# matrix.net
KiCad netlist of a schematic drawn in Altium Designer
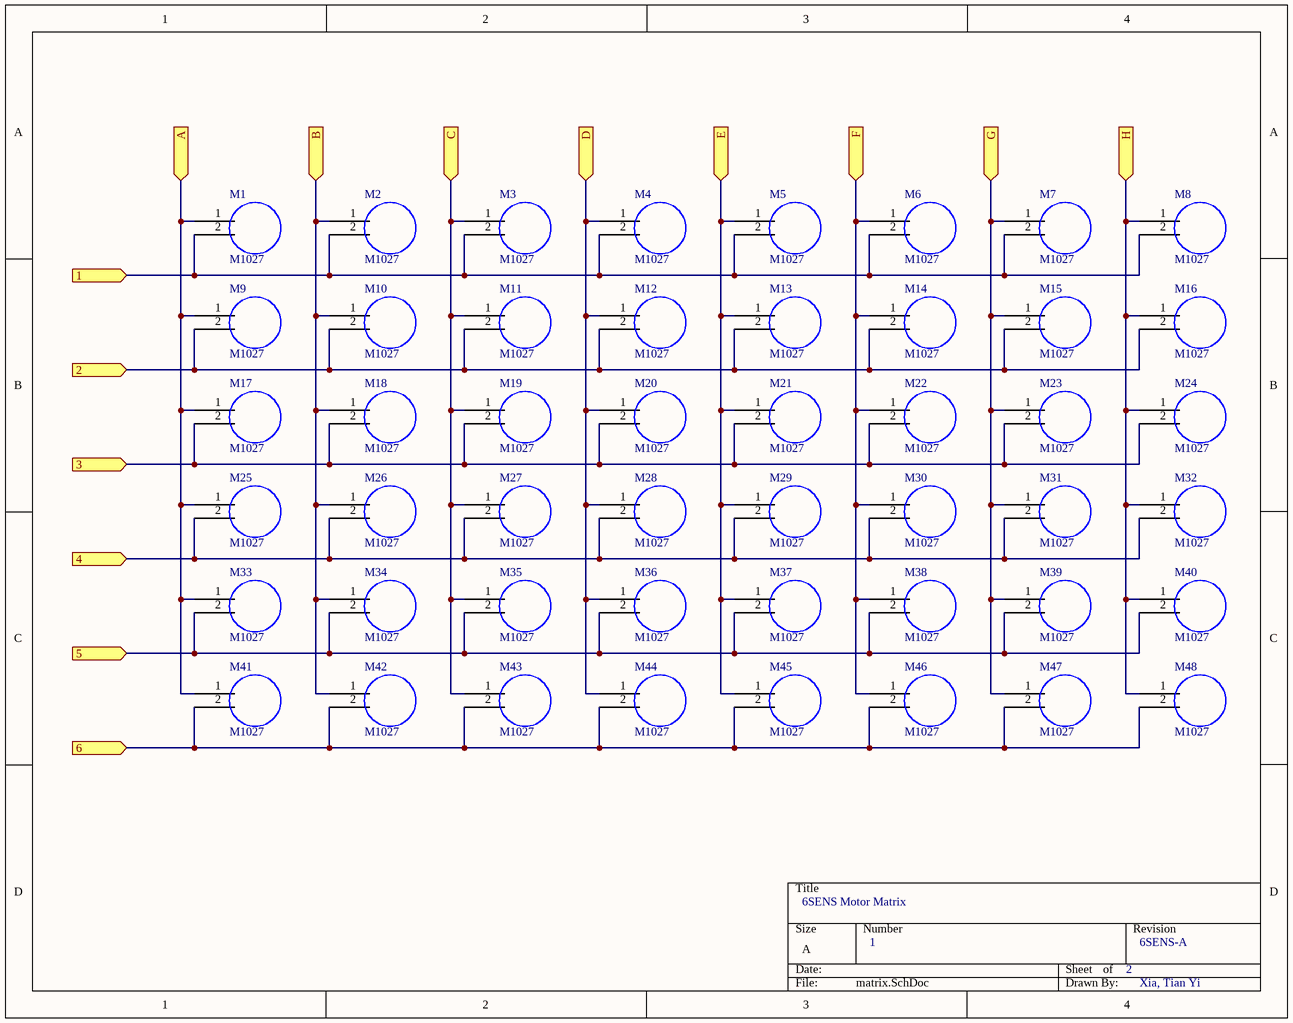
[diagram p0: matrix.SchDoc]

(export (version "E")
  (design (tool "Eeschema 10.0.6"))
  (components
    (comp (ref "M1")
      (value "M1027")
      (footprint "M1027")
      (description "10mm x 2.7mm vibration motor")
      (libsource (lib "6thsense_lib") (part "M1027"))
    )
    (comp (ref "M2")
      (value "M1027")
      (footprint "M1027")
      (description "10mm x 2.7mm vibration motor")
      (libsource (lib "6thsense_lib") (part "M1027"))
    )
    (comp (ref "M3")
      (value "M1027")
      (footprint "M1027")
      (description "10mm x 2.7mm vibration motor")
      (libsource (lib "6thsense_lib") (part "M1027"))
    )
    (comp (ref "M4")
      (value "M1027")
      (footprint "M1027")
      (description "10mm x 2.7mm vibration motor")
      (libsource (lib "6thsense_lib") (part "M1027"))
    )
    (comp (ref "M5")
      (value "M1027")
      (footprint "M1027")
      (description "10mm x 2.7mm vibration motor")
      (libsource (lib "6thsense_lib") (part "M1027"))
    )
    (comp (ref "M6")
      (value "M1027")
      (footprint "M1027")
      (description "10mm x 2.7mm vibration motor")
      (libsource (lib "6thsense_lib") (part "M1027"))
    )
    (comp (ref "M7")
      (value "M1027")
      (footprint "M1027")
      (description "10mm x 2.7mm vibration motor")
      (libsource (lib "6thsense_lib") (part "M1027"))
    )
    (comp (ref "M8")
      (value "M1027")
      (footprint "M1027")
      (description "10mm x 2.7mm vibration motor")
      (libsource (lib "6thsense_lib") (part "M1027"))
    )
    (comp (ref "M9")
      (value "M1027")
      (footprint "M1027")
      (description "10mm x 2.7mm vibration motor")
      (libsource (lib "6thsense_lib") (part "M1027"))
    )
    (comp (ref "M10")
      (value "M1027")
      (footprint "M1027")
      (description "10mm x 2.7mm vibration motor")
      (libsource (lib "6thsense_lib") (part "M1027"))
    )
    (comp (ref "M11")
      (value "M1027")
      (footprint "M1027")
      (description "10mm x 2.7mm vibration motor")
      (libsource (lib "6thsense_lib") (part "M1027"))
    )
    (comp (ref "M12")
      (value "M1027")
      (footprint "M1027")
      (description "10mm x 2.7mm vibration motor")
      (libsource (lib "6thsense_lib") (part "M1027"))
    )
    (comp (ref "M13")
      (value "M1027")
      (footprint "M1027")
      (description "10mm x 2.7mm vibration motor")
      (libsource (lib "6thsense_lib") (part "M1027"))
    )
    (comp (ref "M14")
      (value "M1027")
      (footprint "M1027")
      (description "10mm x 2.7mm vibration motor")
      (libsource (lib "6thsense_lib") (part "M1027"))
    )
    (comp (ref "M15")
      (value "M1027")
      (footprint "M1027")
      (description "10mm x 2.7mm vibration motor")
      (libsource (lib "6thsense_lib") (part "M1027"))
    )
    (comp (ref "M16")
      (value "M1027")
      (footprint "M1027")
      (description "10mm x 2.7mm vibration motor")
      (libsource (lib "6thsense_lib") (part "M1027"))
    )
    (comp (ref "M17")
      (value "M1027")
      (footprint "M1027")
      (description "10mm x 2.7mm vibration motor")
      (libsource (lib "6thsense_lib") (part "M1027"))
    )
    (comp (ref "M18")
      (value "M1027")
      (footprint "M1027")
      (description "10mm x 2.7mm vibration motor")
      (libsource (lib "6thsense_lib") (part "M1027"))
    )
    (comp (ref "M19")
      (value "M1027")
      (footprint "M1027")
      (description "10mm x 2.7mm vibration motor")
      (libsource (lib "6thsense_lib") (part "M1027"))
    )
    (comp (ref "M20")
      (value "M1027")
      (footprint "M1027")
      (description "10mm x 2.7mm vibration motor")
      (libsource (lib "6thsense_lib") (part "M1027"))
    )
    (comp (ref "M21")
      (value "M1027")
      (footprint "M1027")
      (description "10mm x 2.7mm vibration motor")
      (libsource (lib "6thsense_lib") (part "M1027"))
    )
    (comp (ref "M22")
      (value "M1027")
      (footprint "M1027")
      (description "10mm x 2.7mm vibration motor")
      (libsource (lib "6thsense_lib") (part "M1027"))
    )
    (comp (ref "M23")
      (value "M1027")
      (footprint "M1027")
      (description "10mm x 2.7mm vibration motor")
      (libsource (lib "6thsense_lib") (part "M1027"))
    )
    (comp (ref "M24")
      (value "M1027")
      (footprint "M1027")
      (description "10mm x 2.7mm vibration motor")
      (libsource (lib "6thsense_lib") (part "M1027"))
    )
    (comp (ref "M25")
      (value "M1027")
      (footprint "M1027")
      (description "10mm x 2.7mm vibration motor")
      (libsource (lib "6thsense_lib") (part "M1027"))
    )
    (comp (ref "M26")
      (value "M1027")
      (footprint "M1027")
      (description "10mm x 2.7mm vibration motor")
      (libsource (lib "6thsense_lib") (part "M1027"))
    )
    (comp (ref "M27")
      (value "M1027")
      (footprint "M1027")
      (description "10mm x 2.7mm vibration motor")
      (libsource (lib "6thsense_lib") (part "M1027"))
    )
    (comp (ref "M28")
      (value "M1027")
      (footprint "M1027")
      (description "10mm x 2.7mm vibration motor")
      (libsource (lib "6thsense_lib") (part "M1027"))
    )
    (comp (ref "M29")
      (value "M1027")
      (footprint "M1027")
      (description "10mm x 2.7mm vibration motor")
      (libsource (lib "6thsense_lib") (part "M1027"))
    )
    (comp (ref "M30")
      (value "M1027")
      (footprint "M1027")
      (description "10mm x 2.7mm vibration motor")
      (libsource (lib "6thsense_lib") (part "M1027"))
    )
    (comp (ref "M31")
      (value "M1027")
      (footprint "M1027")
      (description "10mm x 2.7mm vibration motor")
      (libsource (lib "6thsense_lib") (part "M1027"))
    )
    (comp (ref "M32")
      (value "M1027")
      (footprint "M1027")
      (description "10mm x 2.7mm vibration motor")
      (libsource (lib "6thsense_lib") (part "M1027"))
    )
    (comp (ref "M33")
      (value "M1027")
      (footprint "M1027")
      (description "10mm x 2.7mm vibration motor")
      (libsource (lib "6thsense_lib") (part "M1027"))
    )
    (comp (ref "M34")
      (value "M1027")
      (footprint "M1027")
      (description "10mm x 2.7mm vibration motor")
      (libsource (lib "6thsense_lib") (part "M1027"))
    )
    (comp (ref "M35")
      (value "M1027")
      (footprint "M1027")
      (description "10mm x 2.7mm vibration motor")
      (libsource (lib "6thsense_lib") (part "M1027"))
    )
    (comp (ref "M36")
      (value "M1027")
      (footprint "M1027")
      (description "10mm x 2.7mm vibration motor")
      (libsource (lib "6thsense_lib") (part "M1027"))
    )
    (comp (ref "M37")
      (value "M1027")
      (footprint "M1027")
      (description "10mm x 2.7mm vibration motor")
      (libsource (lib "6thsense_lib") (part "M1027"))
    )
    (comp (ref "M38")
      (value "M1027")
      (footprint "M1027")
      (description "10mm x 2.7mm vibration motor")
      (libsource (lib "6thsense_lib") (part "M1027"))
    )
    (comp (ref "M39")
      (value "M1027")
      (footprint "M1027")
      (description "10mm x 2.7mm vibration motor")
      (libsource (lib "6thsense_lib") (part "M1027"))
    )
    (comp (ref "M40")
      (value "M1027")
      (footprint "M1027")
      (description "10mm x 2.7mm vibration motor")
      (libsource (lib "6thsense_lib") (part "M1027"))
    )
    (comp (ref "M41")
      (value "M1027")
      (footprint "M1027")
      (description "10mm x 2.7mm vibration motor")
      (libsource (lib "6thsense_lib") (part "M1027"))
    )
    (comp (ref "M42")
      (value "M1027")
      (footprint "M1027")
      (description "10mm x 2.7mm vibration motor")
      (libsource (lib "6thsense_lib") (part "M1027"))
    )
    (comp (ref "M43")
      (value "M1027")
      (footprint "M1027")
      (description "10mm x 2.7mm vibration motor")
      (libsource (lib "6thsense_lib") (part "M1027"))
    )
    (comp (ref "M44")
      (value "M1027")
      (footprint "M1027")
      (description "10mm x 2.7mm vibration motor")
      (libsource (lib "6thsense_lib") (part "M1027"))
    )
    (comp (ref "M45")
      (value "M1027")
      (footprint "M1027")
      (description "10mm x 2.7mm vibration motor")
      (libsource (lib "6thsense_lib") (part "M1027"))
    )
    (comp (ref "M46")
      (value "M1027")
      (footprint "M1027")
      (description "10mm x 2.7mm vibration motor")
      (libsource (lib "6thsense_lib") (part "M1027"))
    )
    (comp (ref "M47")
      (value "M1027")
      (footprint "M1027")
      (description "10mm x 2.7mm vibration motor")
      (libsource (lib "6thsense_lib") (part "M1027"))
    )
    (comp (ref "M48")
      (value "M1027")
      (footprint "M1027")
      (description "10mm x 2.7mm vibration motor")
      (libsource (lib "6thsense_lib") (part "M1027"))
    )
  )
  (nets
    (net (code "1") (name "/1") (class "Default")
      (node (ref "M1") (pin "2") (pinfunction "2_2") (pintype "passive"))
      (node (ref "M2") (pin "2") (pinfunction "2_2") (pintype "passive"))
      (node (ref "M3") (pin "2") (pinfunction "2_2") (pintype "passive"))
      (node (ref "M4") (pin "2") (pinfunction "2_2") (pintype "passive"))
      (node (ref "M5") (pin "2") (pinfunction "2_2") (pintype "passive"))
      (node (ref "M6") (pin "2") (pinfunction "2_2") (pintype "passive"))
      (node (ref "M7") (pin "2") (pinfunction "2_2") (pintype "passive"))
      (node (ref "M8") (pin "2") (pinfunction "2_2") (pintype "passive"))
    )
    (net (code "2") (name "/2") (class "Default")
      (node (ref "M10") (pin "2") (pinfunction "2_2") (pintype "passive"))
      (node (ref "M11") (pin "2") (pinfunction "2_2") (pintype "passive"))
      (node (ref "M12") (pin "2") (pinfunction "2_2") (pintype "passive"))
      (node (ref "M13") (pin "2") (pinfunction "2_2") (pintype "passive"))
      (node (ref "M14") (pin "2") (pinfunction "2_2") (pintype "passive"))
      (node (ref "M15") (pin "2") (pinfunction "2_2") (pintype "passive"))
      (node (ref "M16") (pin "2") (pinfunction "2_2") (pintype "passive"))
      (node (ref "M9") (pin "2") (pinfunction "2_2") (pintype "passive"))
    )
    (net (code "3") (name "/3") (class "Default")
      (node (ref "M17") (pin "2") (pinfunction "2_2") (pintype "passive"))
      (node (ref "M18") (pin "2") (pinfunction "2_2") (pintype "passive"))
      (node (ref "M19") (pin "2") (pinfunction "2_2") (pintype "passive"))
      (node (ref "M20") (pin "2") (pinfunction "2_2") (pintype "passive"))
      (node (ref "M21") (pin "2") (pinfunction "2_2") (pintype "passive"))
      (node (ref "M22") (pin "2") (pinfunction "2_2") (pintype "passive"))
      (node (ref "M23") (pin "2") (pinfunction "2_2") (pintype "passive"))
      (node (ref "M24") (pin "2") (pinfunction "2_2") (pintype "passive"))
    )
    (net (code "4") (name "/4") (class "Default")
      (node (ref "M25") (pin "2") (pinfunction "2_2") (pintype "passive"))
      (node (ref "M26") (pin "2") (pinfunction "2_2") (pintype "passive"))
      (node (ref "M27") (pin "2") (pinfunction "2_2") (pintype "passive"))
      (node (ref "M28") (pin "2") (pinfunction "2_2") (pintype "passive"))
      (node (ref "M29") (pin "2") (pinfunction "2_2") (pintype "passive"))
      (node (ref "M30") (pin "2") (pinfunction "2_2") (pintype "passive"))
      (node (ref "M31") (pin "2") (pinfunction "2_2") (pintype "passive"))
      (node (ref "M32") (pin "2") (pinfunction "2_2") (pintype "passive"))
    )
    (net (code "5") (name "/5") (class "Default")
      (node (ref "M33") (pin "2") (pinfunction "2_2") (pintype "passive"))
      (node (ref "M34") (pin "2") (pinfunction "2_2") (pintype "passive"))
      (node (ref "M35") (pin "2") (pinfunction "2_2") (pintype "passive"))
      (node (ref "M36") (pin "2") (pinfunction "2_2") (pintype "passive"))
      (node (ref "M37") (pin "2") (pinfunction "2_2") (pintype "passive"))
      (node (ref "M38") (pin "2") (pinfunction "2_2") (pintype "passive"))
      (node (ref "M39") (pin "2") (pinfunction "2_2") (pintype "passive"))
      (node (ref "M40") (pin "2") (pinfunction "2_2") (pintype "passive"))
    )
    (net (code "6") (name "/6") (class "Default")
      (node (ref "M41") (pin "2") (pinfunction "2_2") (pintype "passive"))
      (node (ref "M42") (pin "2") (pinfunction "2_2") (pintype "passive"))
      (node (ref "M43") (pin "2") (pinfunction "2_2") (pintype "passive"))
      (node (ref "M44") (pin "2") (pinfunction "2_2") (pintype "passive"))
      (node (ref "M45") (pin "2") (pinfunction "2_2") (pintype "passive"))
      (node (ref "M46") (pin "2") (pinfunction "2_2") (pintype "passive"))
      (node (ref "M47") (pin "2") (pinfunction "2_2") (pintype "passive"))
      (node (ref "M48") (pin "2") (pinfunction "2_2") (pintype "passive"))
    )
    (net (code "7") (name "/A") (class "Default")
      (node (ref "M1") (pin "1") (pinfunction "1_1") (pintype "passive"))
      (node (ref "M17") (pin "1") (pinfunction "1_1") (pintype "passive"))
      (node (ref "M25") (pin "1") (pinfunction "1_1") (pintype "passive"))
      (node (ref "M33") (pin "1") (pinfunction "1_1") (pintype "passive"))
      (node (ref "M41") (pin "1") (pinfunction "1_1") (pintype "passive"))
      (node (ref "M9") (pin "1") (pinfunction "1_1") (pintype "passive"))
    )
    (net (code "8") (name "/B") (class "Default")
      (node (ref "M10") (pin "1") (pinfunction "1_1") (pintype "passive"))
      (node (ref "M18") (pin "1") (pinfunction "1_1") (pintype "passive"))
      (node (ref "M2") (pin "1") (pinfunction "1_1") (pintype "passive"))
      (node (ref "M26") (pin "1") (pinfunction "1_1") (pintype "passive"))
      (node (ref "M34") (pin "1") (pinfunction "1_1") (pintype "passive"))
      (node (ref "M42") (pin "1") (pinfunction "1_1") (pintype "passive"))
    )
    (net (code "9") (name "/C") (class "Default")
      (node (ref "M11") (pin "1") (pinfunction "1_1") (pintype "passive"))
      (node (ref "M19") (pin "1") (pinfunction "1_1") (pintype "passive"))
      (node (ref "M27") (pin "1") (pinfunction "1_1") (pintype "passive"))
      (node (ref "M3") (pin "1") (pinfunction "1_1") (pintype "passive"))
      (node (ref "M35") (pin "1") (pinfunction "1_1") (pintype "passive"))
      (node (ref "M43") (pin "1") (pinfunction "1_1") (pintype "passive"))
    )
    (net (code "10") (name "/D") (class "Default")
      (node (ref "M12") (pin "1") (pinfunction "1_1") (pintype "passive"))
      (node (ref "M20") (pin "1") (pinfunction "1_1") (pintype "passive"))
      (node (ref "M28") (pin "1") (pinfunction "1_1") (pintype "passive"))
      (node (ref "M36") (pin "1") (pinfunction "1_1") (pintype "passive"))
      (node (ref "M4") (pin "1") (pinfunction "1_1") (pintype "passive"))
      (node (ref "M44") (pin "1") (pinfunction "1_1") (pintype "passive"))
    )
    (net (code "11") (name "/E") (class "Default")
      (node (ref "M13") (pin "1") (pinfunction "1_1") (pintype "passive"))
      (node (ref "M21") (pin "1") (pinfunction "1_1") (pintype "passive"))
      (node (ref "M29") (pin "1") (pinfunction "1_1") (pintype "passive"))
      (node (ref "M37") (pin "1") (pinfunction "1_1") (pintype "passive"))
      (node (ref "M45") (pin "1") (pinfunction "1_1") (pintype "passive"))
      (node (ref "M5") (pin "1") (pinfunction "1_1") (pintype "passive"))
    )
    (net (code "12") (name "/F") (class "Default")
      (node (ref "M14") (pin "1") (pinfunction "1_1") (pintype "passive"))
      (node (ref "M22") (pin "1") (pinfunction "1_1") (pintype "passive"))
      (node (ref "M30") (pin "1") (pinfunction "1_1") (pintype "passive"))
      (node (ref "M38") (pin "1") (pinfunction "1_1") (pintype "passive"))
      (node (ref "M46") (pin "1") (pinfunction "1_1") (pintype "passive"))
      (node (ref "M6") (pin "1") (pinfunction "1_1") (pintype "passive"))
    )
    (net (code "13") (name "/G") (class "Default")
      (node (ref "M15") (pin "1") (pinfunction "1_1") (pintype "passive"))
      (node (ref "M23") (pin "1") (pinfunction "1_1") (pintype "passive"))
      (node (ref "M31") (pin "1") (pinfunction "1_1") (pintype "passive"))
      (node (ref "M39") (pin "1") (pinfunction "1_1") (pintype "passive"))
      (node (ref "M47") (pin "1") (pinfunction "1_1") (pintype "passive"))
      (node (ref "M7") (pin "1") (pinfunction "1_1") (pintype "passive"))
    )
    (net (code "14") (name "/H") (class "Default")
      (node (ref "M16") (pin "1") (pinfunction "1_1") (pintype "passive"))
      (node (ref "M24") (pin "1") (pinfunction "1_1") (pintype "passive"))
      (node (ref "M32") (pin "1") (pinfunction "1_1") (pintype "passive"))
      (node (ref "M40") (pin "1") (pinfunction "1_1") (pintype "passive"))
      (node (ref "M48") (pin "1") (pinfunction "1_1") (pintype "passive"))
      (node (ref "M8") (pin "1") (pinfunction "1_1") (pintype "passive"))
    )
  )
)
